# AuxHalfH.net
KiCad netlist of a schematic drawn in Altium Designer
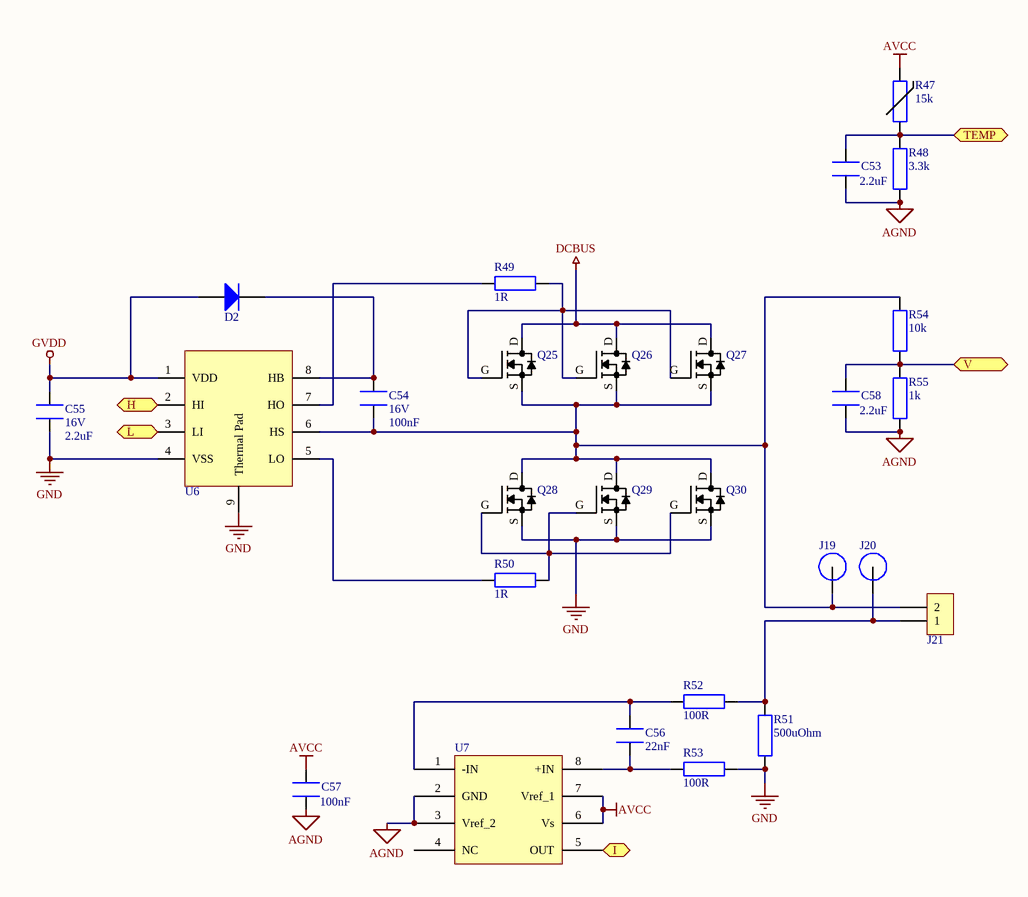
[diagram p0: AuxHalfH.SchDoc]

(export (version "E")
  (design (tool "Eeschema 10.0.6"))
  (components
    (comp (ref "C53")
      (value "2.2uF")
      (footprint "1608[0603]")
      (description "CAP General 0603")
      (libsource (lib "CustomComponents") (part "CAP_0603"))
    )
    (comp (ref "C54")
      (value "16V")
      (footprint "1608[0603]")
      (description "CAP General 0603")
      (fields (field (name "ALTIUM_VALUE") "100nF"))
      (libsource (lib "CustomComponents") (part "CAP_0603"))
    )
    (comp (ref "C55")
      (value "16V")
      (footprint "1608[0603]")
      (description "CAP General 0603")
      (fields (field (name "ALTIUM_VALUE") "2.2uF"))
      (libsource (lib "CustomComponents") (part "CAP_0603"))
    )
    (comp (ref "C56")
      (value "22nF")
      (footprint "1608[0603]")
      (description "CAP General 0603")
      (libsource (lib "CustomComponents") (part "CAP_0603"))
    )
    (comp (ref "C57")
      (value "100nF")
      (footprint "1608[0603]")
      (description "CAP General 0603")
      (libsource (lib "CustomComponents") (part "CAP_0603"))
    )
    (comp (ref "C58")
      (value "2.2uF")
      (footprint "1608[0603]")
      (description "CAP General 0603")
      (libsource (lib "CustomComponents") (part "CAP_0603"))
    )
    (comp (ref "D2")
      (value "~")
      (footprint "DIOM2717X10N")
      (description "Rectifier Diode, Single, 40 V, 1 A, SOD-123FL, 2, 550 mV")
      (libsource (lib "CustomComponents") (part "MBR140SFT1G"))
    )
    (comp (ref "J19")
      (value "~")
      (footprint "M3 Spade Hole")
      (description "M3 Spade Terminal")
      (libsource (lib "CustomComponents") (part "M3 Spade Terminal"))
    )
    (comp (ref "J20")
      (value "~")
      (footprint "M3 Spade Hole")
      (description "M3 Spade Terminal")
      (libsource (lib "CustomComponents") (part "M3 Spade Terminal"))
    )
    (comp (ref "J21")
      (value "~")
      (footprint "MC000054")
      (description "MULTICOMP Wire-To-Board Terminal Block, 2, 600 V, 30 A, 24 AWG, 10 AWG")
      (libsource (lib "CustomComponents") (part "MC000054"))
    )
    (comp (ref "Q25")
      (value "~")
      (footprint "SO8FL_FILL")
      (description "MOSFET, N CH, 30V, 70A, SO-8 FL")
      (libsource (lib "CustomComponents") (part "NTMFS4937NT1G"))
    )
    (comp (ref "Q26")
      (value "~")
      (footprint "SO8FL")
      (description "MOSFET, N CH, 30V, 70A, SO-8 FL")
      (libsource (lib "CustomComponents") (part "NTMFS4937NT1G"))
    )
    (comp (ref "Q27")
      (value "~")
      (footprint "SO8FL_FILL")
      (description "MOSFET, N CH, 30V, 70A, SO-8 FL")
      (libsource (lib "CustomComponents") (part "NTMFS4937NT1G"))
    )
    (comp (ref "Q28")
      (value "~")
      (footprint "SO8FL")
      (description "MOSFET, N CH, 30V, 70A, SO-8 FL")
      (libsource (lib "CustomComponents") (part "NTMFS4937NT1G"))
    )
    (comp (ref "Q29")
      (value "~")
      (footprint "SO8FL")
      (description "MOSFET, N CH, 30V, 70A, SO-8 FL")
      (libsource (lib "CustomComponents") (part "NTMFS4937NT1G"))
    )
    (comp (ref "Q30")
      (value "~")
      (footprint "SO8FL")
      (description "MOSFET, N CH, 30V, 70A, SO-8 FL")
      (libsource (lib "CustomComponents") (part "NTMFS4937NT1G"))
    )
    (comp (ref "R47")
      (value "15k")
      (footprint "RESC1608X06L")
      (description "THERMISTOR, 15K, 5%, SMD, NTC")
      (libsource (lib "CustomComponents") (part "NTCS0603E3153JMT"))
    )
    (comp (ref "R48")
      (value "3.3k")
      (footprint "RESC1608X55N")
      (description "RES General 1% 0603")
      (libsource (lib "CustomComponents") (part "RES_0603"))
    )
    (comp (ref "R49")
      (value "1R")
      (footprint "RESC1608X55N")
      (description "RES General 1% 0603")
      (libsource (lib "CustomComponents") (part "RES_0603"))
    )
    (comp (ref "R50")
      (value "1R")
      (footprint "RESC1608X55N")
      (description "RES General 1% 0603")
      (libsource (lib "CustomComponents") (part "RES_0603"))
    )
    (comp (ref "R51")
      (value "500uOhm")
      (footprint "RESC6432X09N")
      (description "RES SMD 0.0005 OHM 1% 3W 2512")
      (libsource (lib "CustomComponents") (part "CSR2512C0R0005F"))
    )
    (comp (ref "R52")
      (value "100R")
      (footprint "RESC1608X55N")
      (description "RES General 1% 0603")
      (libsource (lib "CustomComponents") (part "RES_0603"))
    )
    (comp (ref "R53")
      (value "100R")
      (footprint "RESC1608X55N")
      (description "RES General 1% 0603")
      (libsource (lib "CustomComponents") (part "RES_0603"))
    )
    (comp (ref "R54")
      (value "10k")
      (footprint "RESC1608X55N")
      (description "RES General 1% 0603")
      (libsource (lib "CustomComponents") (part "RES_0603"))
    )
    (comp (ref "R55")
      (value "1k")
      (footprint "RESC1608X55N")
      (description "RES General 1% 0603")
      (libsource (lib "CustomComponents") (part "RES_0603"))
    )
    (comp (ref "U6")
      (value "~")
      (footprint "SON80P400X80_HS-9N")
      (description "DRIVER, MOSFET, HALF BRIDGE, WSON-8, 1A")
      (libsource (lib "CustomComponents") (part "LM5109BSD/NOPB"))
    )
    (comp (ref "U7")
      (value "~")
      (footprint "SOIC127P600X175-8N")
      (description "ANALOG DEVICES Current Sense Amplifier, Bidirectional, 1, 130 µA, NSOIC")
      (libsource (lib "CustomComponents") (part "AD8418WBRZ"))
    )
  )
  (nets
    (net (code "1") (name "/H") (class "Default")
      (node (ref "U6") (pin "2") (pinfunction "HI_2") (pintype "passive"))
    )
    (net (code "2") (name "/I") (class "Default")
      (node (ref "U7") (pin "5") (pinfunction "OUT_5") (pintype "passive"))
    )
    (net (code "3") (name "/L") (class "Default")
      (node (ref "U6") (pin "3") (pinfunction "LI_3") (pintype "passive"))
    )
    (net (code "4") (name "/TEMP") (class "Default")
      (node (ref "C53") (pin "2") (pinfunction "2_2") (pintype "passive"))
      (node (ref "R47") (pin "1") (pinfunction "0_1") (pintype "passive"))
      (node (ref "R48") (pin "1") (pinfunction "0_1") (pintype "passive"))
    )
    (net (code "5") (name "/V") (class "Default")
      (node (ref "C58") (pin "2") (pinfunction "2_2") (pintype "passive"))
      (node (ref "R54") (pin "2") (pinfunction "0_2") (pintype "passive"))
      (node (ref "R55") (pin "1") (pinfunction "0_1") (pintype "passive"))
    )
    (net (code "6") (name "AGND") (class "Default")
      (node (ref "C53") (pin "1") (pinfunction "1_1") (pintype "passive"))
      (node (ref "C57") (pin "2") (pinfunction "2_2") (pintype "passive"))
      (node (ref "C58") (pin "1") (pinfunction "1_1") (pintype "passive"))
      (node (ref "R48") (pin "2") (pinfunction "0_2") (pintype "passive"))
      (node (ref "R55") (pin "2") (pinfunction "0_2") (pintype "passive"))
      (node (ref "U7") (pin "2") (pinfunction "GND_2") (pintype "passive"))
      (node (ref "U7") (pin "3") (pinfunction "Vref_2_3") (pintype "passive"))
    )
    (net (code "7") (name "AVCC") (class "Default")
      (node (ref "C57") (pin "1") (pinfunction "1_1") (pintype "passive"))
      (node (ref "R47") (pin "2") (pinfunction "0_2") (pintype "passive"))
      (node (ref "U7") (pin "6") (pinfunction "Vs_6") (pintype "passive"))
      (node (ref "U7") (pin "7") (pinfunction "Vref_1_7") (pintype "passive"))
    )
    (net (code "8") (name "DCBUS") (class "Default")
      (node (ref "Q25") (pin "D") (pinfunction "D_D") (pintype "passive"))
      (node (ref "Q26") (pin "D") (pinfunction "D_D") (pintype "passive"))
      (node (ref "Q27") (pin "D") (pinfunction "D_D") (pintype "passive"))
    )
    (net (code "9") (name "GND") (class "Default")
      (node (ref "C55") (pin "1") (pinfunction "1_1") (pintype "passive"))
      (node (ref "Q28") (pin "S") (pinfunction "S_S") (pintype "passive"))
      (node (ref "Q29") (pin "S") (pinfunction "S_S") (pintype "passive"))
      (node (ref "Q30") (pin "S") (pinfunction "S_S") (pintype "passive"))
      (node (ref "R51") (pin "2") (pinfunction "0_2") (pintype "passive"))
      (node (ref "R53") (pin "2") (pinfunction "0_2") (pintype "passive"))
      (node (ref "U6") (pin "4") (pinfunction "VSS_4") (pintype "passive"))
      (node (ref "U6") (pin "9") (pinfunction "Thermal_Pad_9") (pintype "passive"))
    )
    (net (code "10") (name "GVDD") (class "Default")
      (node (ref "C55") (pin "2") (pinfunction "2_2") (pintype "passive"))
      (node (ref "D2") (pin "A") (pinfunction "A_A") (pintype "passive"))
      (node (ref "U6") (pin "1") (pinfunction "VDD_1") (pintype "passive"))
    )
    (net (code "11") (name "Net-(J20-Pad1)") (class "Default")
      (node (ref "J20") (pin "1") (pinfunction "1_1") (pintype "passive"))
      (node (ref "J21") (pin "1") (pinfunction "1_1") (pintype "passive"))
      (node (ref "R51") (pin "1") (pinfunction "0_1") (pintype "passive"))
      (node (ref "R52") (pin "2") (pinfunction "0_2") (pintype "passive"))
    )
    (net (code "12") (name "Net-(Q25-PadG)") (class "Default")
      (node (ref "Q25") (pin "G") (pinfunction "G_G") (pintype "passive"))
      (node (ref "Q26") (pin "G") (pinfunction "G_G") (pintype "passive"))
      (node (ref "Q27") (pin "G") (pinfunction "G_G") (pintype "passive"))
      (node (ref "R49") (pin "2") (pinfunction "0_2") (pintype "passive"))
    )
    (net (code "13") (name "Net-(Q28-PadG)") (class "Default")
      (node (ref "Q28") (pin "G") (pinfunction "G_G") (pintype "passive"))
      (node (ref "Q29") (pin "G") (pinfunction "G_G") (pintype "passive"))
      (node (ref "Q30") (pin "G") (pinfunction "G_G") (pintype "passive"))
      (node (ref "R50") (pin "2") (pinfunction "0_2") (pintype "passive"))
    )
    (net (code "14") (name "Net-(U6-HB)") (class "Default")
      (node (ref "C54") (pin "1") (pinfunction "1_1") (pintype "passive"))
      (node (ref "D2") (pin "K") (pinfunction "K_K") (pintype "passive"))
      (node (ref "U6") (pin "8") (pinfunction "HB_8") (pintype "passive"))
    )
    (net (code "15") (name "Net-(U6-HO)") (class "Default")
      (node (ref "R49") (pin "1") (pinfunction "0_1") (pintype "passive"))
      (node (ref "U6") (pin "7") (pinfunction "HO_7") (pintype "passive"))
    )
    (net (code "16") (name "Net-(U6-HS)") (class "Default")
      (node (ref "C54") (pin "2") (pinfunction "2_2") (pintype "passive"))
      (node (ref "J19") (pin "1") (pinfunction "1_1") (pintype "passive"))
      (node (ref "J21") (pin "2") (pinfunction "2_2") (pintype "passive"))
      (node (ref "Q25") (pin "S") (pinfunction "S_S") (pintype "passive"))
      (node (ref "Q26") (pin "S") (pinfunction "S_S") (pintype "passive"))
      (node (ref "Q27") (pin "S") (pinfunction "S_S") (pintype "passive"))
      (node (ref "Q28") (pin "D") (pinfunction "D_D") (pintype "passive"))
      (node (ref "Q29") (pin "D") (pinfunction "D_D") (pintype "passive"))
      (node (ref "Q30") (pin "D") (pinfunction "D_D") (pintype "passive"))
      (node (ref "R54") (pin "1") (pinfunction "0_1") (pintype "passive"))
      (node (ref "U6") (pin "6") (pinfunction "HS_6") (pintype "passive"))
    )
    (net (code "17") (name "Net-(U6-LO)") (class "Default")
      (node (ref "R50") (pin "1") (pinfunction "0_1") (pintype "passive"))
      (node (ref "U6") (pin "5") (pinfunction "LO_5") (pintype "passive"))
    )
    (net (code "18") (name "Net-(U7-+IN)") (class "Default")
      (node (ref "C56") (pin "2") (pinfunction "2_2") (pintype "passive"))
      (node (ref "R53") (pin "1") (pinfunction "0_1") (pintype "passive"))
      (node (ref "U7") (pin "8") (pinfunction "+IN_8") (pintype "passive"))
    )
    (net (code "19") (name "Net-(U7--IN)") (class "Default")
      (node (ref "C56") (pin "1") (pinfunction "1_1") (pintype "passive"))
      (node (ref "R52") (pin "1") (pinfunction "0_1") (pintype "passive"))
      (node (ref "U7") (pin "1") (pinfunction "-IN_1") (pintype "passive"))
    )
    (net (code "20") (name "unconnected-(U7-NC-Pad4)") (class "Default")
      (node (ref "U7") (pin "4") (pinfunction "NC_4") (pintype "passive"))
    )
  )
)
